# 04_-CPU-JTAG_POWER.net
KiCad netlist of a schematic drawn in Altium Designer
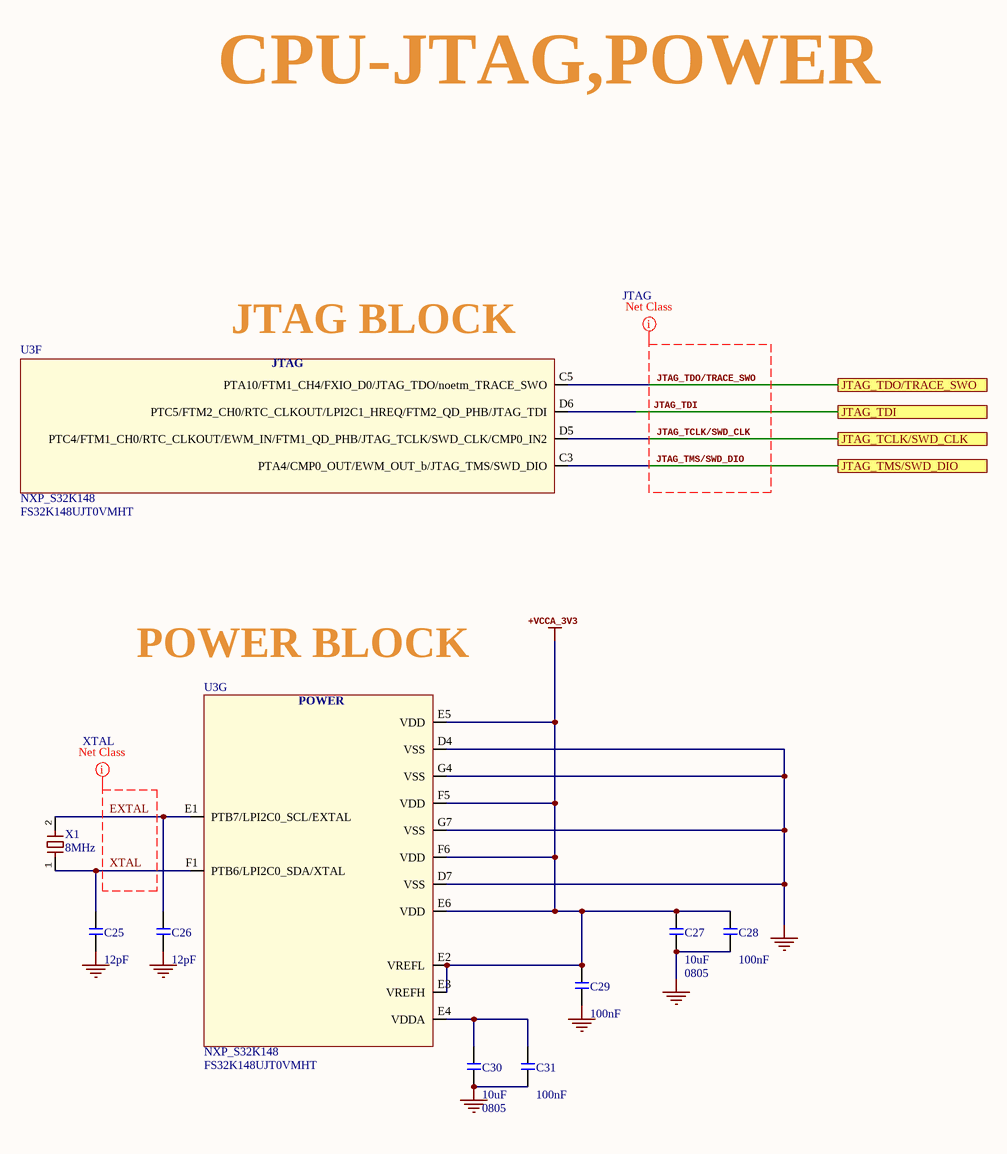
[diagram p0: [04]-CPU-JTAG,POWER.SchDoc]

(export (version "E")
  (design (tool "Eeschema 10.0.6"))
  (components
    (comp (ref "C25")
      (value "12pF")
      (footprint "CAP0402")
      (description "Cap Ceramic 12pF 50V C0G 2% Pad SMD 0402 125C Automotive T/R")
      (fields
        (field (name "MANUFACTURER") "Murata")
        (field (name "MANUFACTURER PART NUMBER") "GCQ1555C1H120GB01D")
      )
      (libsource (lib "altium-import") (part "root_0_GCQ1555C1H120GB01D_"))
    )
    (comp (ref "C26")
      (value "12pF")
      (footprint "CAP0402")
      (description "Cap Ceramic 12pF 50V C0G 2% Pad SMD 0402 125C Automotive T/R")
      (fields
        (field (name "MANUFACTURER") "Murata")
        (field (name "MANUFACTURER PART NUMBER") "GCQ1555C1H120GB01D")
      )
      (libsource (lib "altium-import") (part "root_0_GCQ1555C1H120GB01D_"))
    )
    (comp (ref "C27")
      (value "CGA4J1X5R1C106K125AC")
      (footprint "CAP0805")
      (description "CGA Series 0805 10 uF 16 V ±10 % Tolerance X5R SMT Multilayer Ceramic Capacitor")
      (fields
        (field (name "MANUFACTURER") "TDK")
        (field (name "TOLERANCE") "10%")
        (field (name "CAPACITANCE") "10uF")
        (field (name "CASE/PACKAGE") "0805")
      )
      (libsource (lib "altium-import") (part "root_0_CGA4J1X5R1C106K125AC_"))
    )
    (comp (ref "C28")
      (value "GCM155R71C104KA55D")
      (footprint "CAP0402")
      (description "Multilayer Ceramic Capacitors (MLCC) - SMD/SMT 0402 0.1uF 16volts X7R 10%")
      (fields
        (field (name "MANUFACTURER") "Murata")
        (field (name "TOLERANCE") "10%")
        (field (name "CAPACITANCE") "100nF")
      )
      (libsource (lib "altium-import") (part "root_0_GCM155R71C104KA55D_"))
    )
    (comp (ref "C29")
      (value "GCM155R71C104KA55D")
      (footprint "CAP0402")
      (description "Multilayer Ceramic Capacitors (MLCC) - SMD/SMT 0402 0.1uF 16volts X7R 10%")
      (fields
        (field (name "MANUFACTURER") "Murata")
        (field (name "TOLERANCE") "10%")
        (field (name "CAPACITANCE") "100nF")
      )
      (libsource (lib "altium-import") (part "root_0_GCM155R71C104KA55D_"))
    )
    (comp (ref "C30")
      (value "CGA4J1X5R1C106K125AC")
      (footprint "CAP0805")
      (description "CGA Series 0805 10 uF 16 V ±10 % Tolerance X5R SMT Multilayer Ceramic Capacitor")
      (fields
        (field (name "MANUFACTURER") "TDK")
        (field (name "TOLERANCE") "10%")
        (field (name "CAPACITANCE") "10uF")
        (field (name "CASE/PACKAGE") "0805")
      )
      (libsource (lib "altium-import") (part "root_0_CGA4J1X5R1C106K125AC_"))
    )
    (comp (ref "C31")
      (value "GCM155R71C104KA55D")
      (footprint "CAP0402")
      (description "Multilayer Ceramic Capacitors (MLCC) - SMD/SMT 0402 0.1uF 16volts X7R 10%")
      (fields
        (field (name "MANUFACTURER") "Murata")
        (field (name "TOLERANCE") "10%")
        (field (name "CAPACITANCE") "100nF")
      )
      (libsource (lib "altium-import") (part "root_0_GCM155R71C104KA55D_"))
    )
    (comp (ref "U3")
      (value "NXP_S32K148")
      (footprint "WEONREFERENCEPLATFORM_100MAPBGA")
      (fields
        (field (name "MANUFACTURER") "NXP Semiconductors")
        (field (name "MANUFACTURER PART NUMBER") "FS32K148UJT0VMHT")
      )
      (libsource (lib "WeOnReferenceBoard") (part "NXP_S32K148"))
    )
    (comp (ref "X1")
      (value "8MHz")
      (footprint "CRYSTAL_NX3225")
      (description "Crystal 8MHZ 8PF SMD")
      (fields
        (field (name "MANUFACTURER") "NDK")
        (field (name "MANUFACTURER PART NUMBER") "NX3225GD-8MHZ-EXS00A-CG04874")
      )
      (libsource (lib "altium-import") (part "root_1_NX3225GD-8MHZ-EXS00A-CG04874_"))
    )
  )
  (nets
    (net (code "1") (name "+VCCA_3V3") (class "Default")
      (node (ref "C27") (pin "1") (pinfunction "1_1") (pintype "passive"))
      (node (ref "C28") (pin "1") (pinfunction "1_1") (pintype "passive"))
      (node (ref "C29") (pin "1") (pinfunction "1_1") (pintype "passive"))
      (node (ref "U3") (pin "E2") (pinfunction "VREFL_E2") (pintype "passive"))
      (node (ref "U3") (pin "E3") (pinfunction "VREFH_E3") (pintype "passive"))
      (node (ref "U3") (pin "E5") (pinfunction "VDD_E5") (pintype "passive"))
      (node (ref "U3") (pin "E6") (pinfunction "VDD_E6") (pintype "passive"))
      (node (ref "U3") (pin "F5") (pinfunction "VDD_F5") (pintype "passive"))
      (node (ref "U3") (pin "F6") (pinfunction "VDD_F6") (pintype "passive"))
    )
    (net (code "2") (name "/EXTAL") (class "Default")
      (node (ref "C26") (pin "1") (pinfunction "1_1") (pintype "passive"))
      (node (ref "U3") (pin "E1") (pinfunction "PTB7/LPI2C0_SCL/EXTAL_E1") (pintype "passive"))
      (node (ref "X1") (pin "2") (pinfunction "2_2") (pintype "passive"))
    )
    (net (code "3") (name "/JTAG_TCLK{slash}SWD_CLK") (class "Default")
      (node (ref "U3") (pin "D5") (pinfunction "PTC4/FTM1_CH0/RTC_CLKOUT/EWM_IN/FTM1_QD_PHB/JTAG_TCLK/SWD_CLK/CMP0_IN2_D5") (pintype "passive"))
    )
    (net (code "4") (name "/JTAG_TDI") (class "Default")
      (node (ref "U3") (pin "D6") (pinfunction "PTC5/FTM2_CH0/RTC_CLKOUT/LPI2C1_HREQ/FTM2_QD_PHB/JTAG_TDI_D6") (pintype "passive"))
    )
    (net (code "5") (name "/JTAG_TDO{slash}TRACE_SWO") (class "Default")
      (node (ref "U3") (pin "C5") (pinfunction "PTA10/FTM1_CH4/FXIO_D0/JTAG_TDO/noetm_TRACE_SWO_C5") (pintype "passive"))
    )
    (net (code "6") (name "/JTAG_TMS{slash}SWD_DIO") (class "Default")
      (node (ref "U3") (pin "C3") (pinfunction "PTA4/CMP0_OUT/EWM_OUT_b/JTAG_TMS/SWD_DIO_C3") (pintype "passive"))
    )
    (net (code "7") (name "/XTAL") (class "Default")
      (node (ref "C25") (pin "1") (pinfunction "1_1") (pintype "passive"))
      (node (ref "U3") (pin "F1") (pinfunction "PTB6/LPI2C0_SDA/XTAL_F1") (pintype "passive"))
      (node (ref "X1") (pin "1") (pinfunction "1_1") (pintype "passive"))
    )
    (net (code "8") (name "GND") (class "Default")
      (node (ref "C25") (pin "2") (pinfunction "2_2") (pintype "passive"))
      (node (ref "C26") (pin "2") (pinfunction "2_2") (pintype "passive"))
      (node (ref "C27") (pin "2") (pinfunction "2_2") (pintype "passive"))
      (node (ref "C28") (pin "2") (pinfunction "2_2") (pintype "passive"))
      (node (ref "C29") (pin "2") (pinfunction "2_2") (pintype "passive"))
      (node (ref "C30") (pin "2") (pinfunction "2_2") (pintype "passive"))
      (node (ref "C31") (pin "2") (pinfunction "2_2") (pintype "passive"))
      (node (ref "U3") (pin "D4") (pinfunction "VSS_D4") (pintype "passive"))
      (node (ref "U3") (pin "D7") (pinfunction "VSS_D7") (pintype "passive"))
      (node (ref "U3") (pin "G4") (pinfunction "VSS_G4") (pintype "passive"))
      (node (ref "U3") (pin "G7") (pinfunction "VSS_G7") (pintype "passive"))
    )
    (net (code "9") (name "Net-(U3G-VDDA)") (class "Default")
      (node (ref "C30") (pin "1") (pinfunction "1_1") (pintype "passive"))
      (node (ref "C31") (pin "1") (pinfunction "1_1") (pintype "passive"))
      (node (ref "U3") (pin "E4") (pinfunction "VDDA_E4") (pintype "passive"))
    )
  )
)
